# pc_heartypatch_v2_3.net
KiCad netlist of a schematic drawn in EAGLE
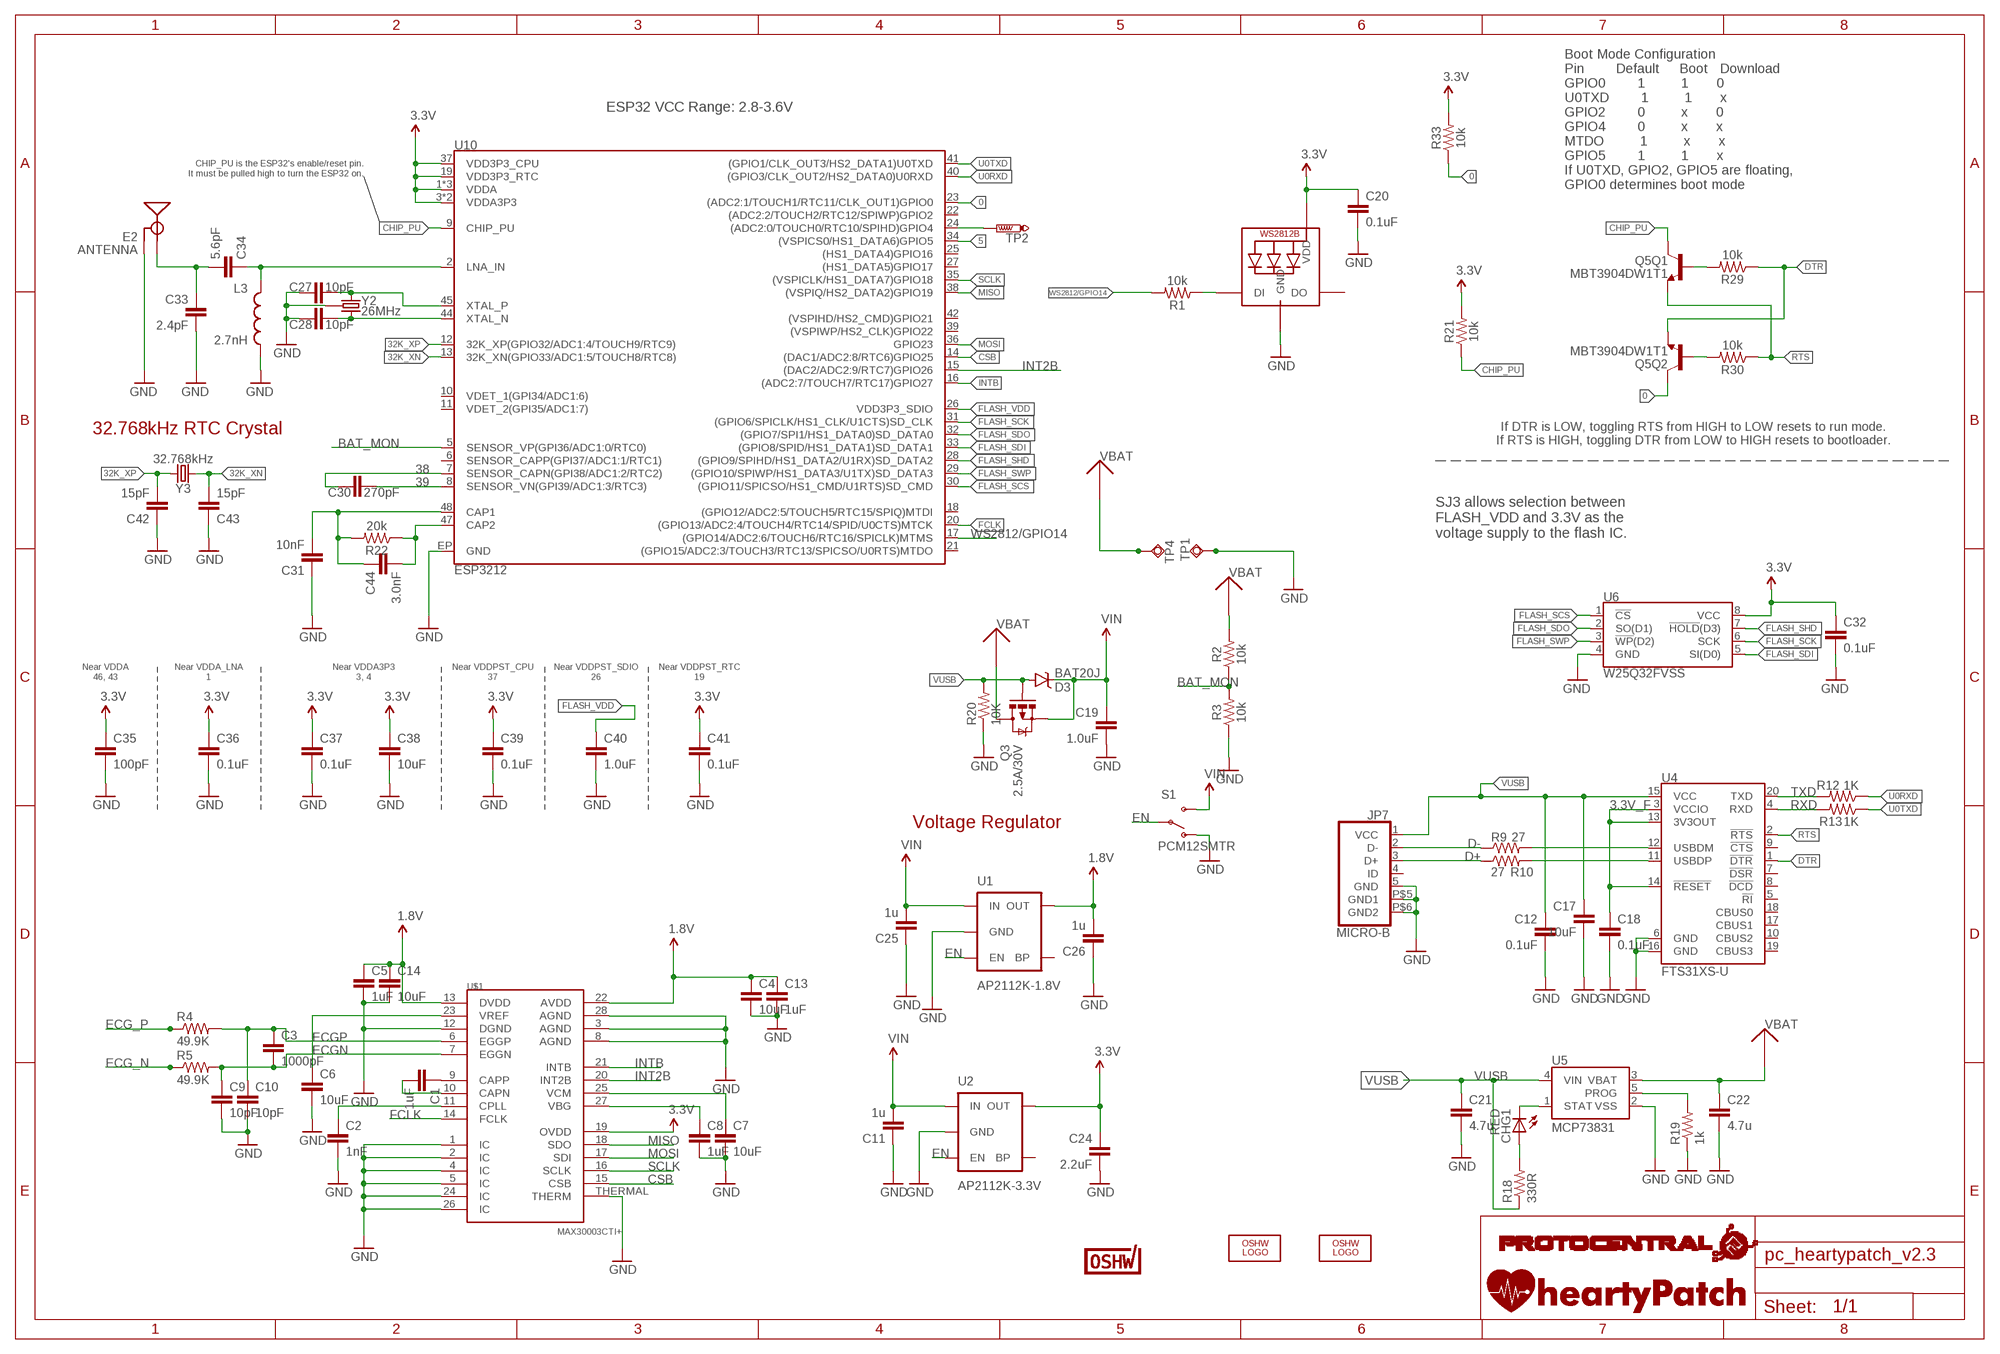
[diagram p0: schematic, sheet 1]

(export (version "E")
  (design (tool "Eeschema 10.0.6"))
  (components
    (comp (ref "C1")
      (value "1uF")
      (footprint "eagle-import:C0603")
      (libsource (lib "eagle-import") (part "C-EUC0603"))
    )
    (comp (ref "C2")
      (value "1nF")
      (footprint "eagle-import:C0603")
      (libsource (lib "eagle-import") (part "C-EUC0603"))
    )
    (comp (ref "C3")
      (value "1000pF")
      (footprint "eagle-import:C0402")
      (libsource (lib "eagle-import") (part "C-EUC0402"))
    )
    (comp (ref "C4")
      (value "10uF")
      (footprint "eagle-import:C0805")
      (libsource (lib "eagle-import") (part "C-EUC0805"))
    )
    (comp (ref "C5")
      (value "1uF")
      (footprint "eagle-import:C0402")
      (libsource (lib "eagle-import") (part "C-EUC0402"))
    )
    (comp (ref "C6")
      (value "10uF")
      (footprint "eagle-import:C0805")
      (libsource (lib "eagle-import") (part "C-EUC0805"))
    )
    (comp (ref "C7")
      (value "10uF")
      (footprint "eagle-import:C0805")
      (libsource (lib "eagle-import") (part "C-EUC0805"))
    )
    (comp (ref "C8")
      (value "1uF")
      (footprint "eagle-import:C0805")
      (libsource (lib "eagle-import") (part "C-EUC0805"))
    )
    (comp (ref "C9")
      (value "10pF")
      (footprint "eagle-import:C0402")
      (libsource (lib "eagle-import") (part "C-EUC0402"))
    )
    (comp (ref "C10")
      (value "10pF")
      (footprint "eagle-import:C0402")
      (libsource (lib "eagle-import") (part "C-EUC0402"))
    )
    (comp (ref "C11")
      (value "1u")
      (footprint "eagle-import:C0402")
      (libsource (lib "eagle-import") (part "C-EUC0402"))
    )
    (comp (ref "C12")
      (value "0.1uF")
      (footprint "eagle-import:C0402")
      (libsource (lib "eagle-import") (part "C-EUC0402"))
    )
    (comp (ref "C13")
      (value "1uF")
      (footprint "eagle-import:C0805")
      (libsource (lib "eagle-import") (part "C-EUC0805"))
    )
    (comp (ref "C14")
      (value "10uF")
      (footprint "eagle-import:C0603")
      (libsource (lib "eagle-import") (part "C-EUC0603"))
    )
    (comp (ref "C17")
      (value "10uF")
      (footprint "eagle-import:C0805")
      (libsource (lib "eagle-import") (part "C-EUC0805"))
    )
    (comp (ref "C18")
      (value "0.1uF")
      (footprint "eagle-import:C0402")
      (libsource (lib "eagle-import") (part "C-EUC0402"))
    )
    (comp (ref "C19")
      (value "1.0uF")
      (footprint "eagle-import:C0402")
      (libsource (lib "eagle-import") (part "C-EUC0402"))
    )
    (comp (ref "C20")
      (value "0.1uF")
      (footprint "eagle-import:0603")
      (libsource (lib "eagle-import") (part "0.1UF-0603-25V-(+80/-20%)"))
    )
    (comp (ref "C21")
      (value "4.7u")
      (footprint "eagle-import:C0805")
      (libsource (lib "eagle-import") (part "C-EUC0805"))
    )
    (comp (ref "C22")
      (value "4.7u")
      (footprint "eagle-import:C0805")
      (libsource (lib "eagle-import") (part "C-EUC0805"))
    )
    (comp (ref "C24")
      (value "2.2uF")
      (footprint "eagle-import:C0402")
      (libsource (lib "eagle-import") (part "C-EUC0402"))
    )
    (comp (ref "C25")
      (value "1u")
      (footprint "eagle-import:C0402")
      (libsource (lib "eagle-import") (part "C-EUC0402"))
    )
    (comp (ref "C26")
      (value "1u")
      (footprint "eagle-import:C0402")
      (libsource (lib "eagle-import") (part "C-EUC0402"))
    )
    (comp (ref "C27")
      (value "10pF")
      (footprint "eagle-import:0603")
      (libsource (lib "eagle-import") (part "10PF-0603-50V-5%"))
    )
    (comp (ref "C28")
      (value "10pF")
      (footprint "eagle-import:0603")
      (libsource (lib "eagle-import") (part "10PF-0603-50V-5%"))
    )
    (comp (ref "C30")
      (value "270pF")
      (footprint "eagle-import:0603")
      (libsource (lib "eagle-import") (part "270PF-50V-5%(0603)"))
    )
    (comp (ref "C31")
      (value "10nF")
      (footprint "eagle-import:0603")
      (libsource (lib "eagle-import") (part "10NF-0603-50V-10%"))
    )
    (comp (ref "C32")
      (value "0.1uF")
      (footprint "eagle-import:0402")
      (libsource (lib "eagle-import") (part "0.1UF-0402-16V-10%"))
    )
    (comp (ref "C33")
      (value "2.4pF")
      (footprint "eagle-import:0603")
      (libsource (lib "eagle-import") (part "2.4PF-0603-50V-5%"))
    )
    (comp (ref "C34")
      (value "5.6pF")
      (footprint "eagle-import:0603")
      (libsource (lib "eagle-import") (part "5.6PF-50V-5%(0603)"))
    )
    (comp (ref "C35")
      (value "100pF")
      (footprint "eagle-import:0603")
      (libsource (lib "eagle-import") (part "100PF-0603-50V-5%"))
    )
    (comp (ref "C36")
      (value "0.1uF")
      (footprint "eagle-import:0603")
      (libsource (lib "eagle-import") (part "0.1UF-0603-25V-(+80/-20%)"))
    )
    (comp (ref "C37")
      (value "0.1uF")
      (footprint "eagle-import:0603")
      (libsource (lib "eagle-import") (part "0.1UF-0603-25V-(+80/-20%)"))
    )
    (comp (ref "C38")
      (value "10uF")
      (footprint "eagle-import:0603")
      (libsource (lib "eagle-import") (part "10UF-0603-6.3V-20%"))
    )
    (comp (ref "C39")
      (value "0.1uF")
      (footprint "eagle-import:0402")
      (libsource (lib "eagle-import") (part "0.1UF-0402-16V-10%"))
    )
    (comp (ref "C40")
      (value "1.0uF")
      (footprint "eagle-import:0603")
      (libsource (lib "eagle-import") (part "1.0UF-0603-16V-10%"))
    )
    (comp (ref "C41")
      (value "0.1uF")
      (footprint "eagle-import:0603")
      (libsource (lib "eagle-import") (part "0.1UF-0603-25V-(+80/-20%)"))
    )
    (comp (ref "C42")
      (value "15pF")
      (footprint "eagle-import:0603")
      (libsource (lib "eagle-import") (part "15PF-0603-50V-5%"))
    )
    (comp (ref "C43")
      (value "15pF")
      (footprint "eagle-import:0603")
      (libsource (lib "eagle-import") (part "15PF-0603-50V-5%"))
    )
    (comp (ref "C44")
      (value "3.0nF")
      (footprint "eagle-import:0603")
      (libsource (lib "eagle-import") (part "3.0NF-0603-50V-5%"))
    )
    (comp (ref "CHG1")
      (value "RED")
      (footprint "eagle-import:CHIPLED_0603")
      (libsource (lib "eagle-import") (part "LEDCHIPLED_0603"))
    )
    (comp (ref "D3")
      (value "BAT20J")
      (footprint "eagle-import:SOD-323")
      (libsource (lib "eagle-import") (part "DIODE-SCHOTTKY-BAT20J"))
    )
    (comp (ref "E2")
      (value "ANTENNA")
      (footprint "eagle-import:TRACE_ANTENNA_2.4GHZ_25.7MM_TUNED")
      (libsource (lib "eagle-import") (part "ANTENNATRACE-TUNED"))
    )
    (comp (ref "JP7")
      (value "MICRO-B")
      (footprint "eagle-import:MICRO-B")
      (libsource (lib "eagle-import") (part "MICRO-B"))
    )
    (comp (ref "L3")
      (value "2.7nH")
      (footprint "eagle-import:0603")
      (libsource (lib "eagle-import") (part "INDUCTOR0603"))
    )
    (comp (ref "LED1")
      (value "WS2812B5050")
      (footprint "eagle-import:WS2812B")
      (libsource (lib "eagle-import") (part "WS2812B5050"))
    )
    (comp (ref "LOGO1")
      (value "OSHW_LOGO_FILLX0200-NT")
      (footprint "eagle-import:OSHW_FILLX200_NOTEXT")
      (libsource (lib "eagle-import") (part "OSHW_LOGO_FILLX0200-NT"))
    )
    (comp (ref "LOGO2")
      (value "OSHW_LOGO_FILLX0200-NT")
      (footprint "eagle-import:OSHW_FILLX200_NOTEXT")
      (libsource (lib "eagle-import") (part "OSHW_LOGO_FILLX0200-NT"))
    )
    (comp (ref "Q3")
      (value "2.5A/30V")
      (footprint "eagle-import:SOT23-3")
      (libsource (lib "eagle-import") (part "MOSFET-PCHANNELDMG2307L"))
    )
    (comp (ref "Q5")
      (value "MBT3904DW1T1")
      (footprint "eagle-import:SC70-6")
      (libsource (lib "eagle-import") (part "MBT3904DW1T1"))
    )
    (comp (ref "R1")
      (value "10k")
      (footprint "eagle-import:0603")
      (libsource (lib "eagle-import") (part "10KOHM-1/10W-1%(0603)0603"))
    )
    (comp (ref "R2")
      (value "10k")
      (footprint "eagle-import:0603")
      (libsource (lib "eagle-import") (part "10KOHM-1/10W-1%(0603)0603"))
    )
    (comp (ref "R3")
      (value "10k")
      (footprint "eagle-import:0603")
      (libsource (lib "eagle-import") (part "10KOHM-1/10W-1%(0603)0603"))
    )
    (comp (ref "R4")
      (value "49.9K")
      (footprint "eagle-import:0805")
      (libsource (lib "eagle-import") (part "RESISTOR0805-RES"))
    )
    (comp (ref "R5")
      (value "49.9K")
      (footprint "eagle-import:0805")
      (libsource (lib "eagle-import") (part "RESISTOR0805-RES"))
    )
    (comp (ref "R9")
      (value "27")
      (footprint "eagle-import:R0402")
      (libsource (lib "eagle-import") (part "R-US_R0402"))
    )
    (comp (ref "R10")
      (value "27")
      (footprint "eagle-import:R0402")
      (libsource (lib "eagle-import") (part "R-US_R0402"))
    )
    (comp (ref "R12")
      (value "1K")
      (footprint "eagle-import:R0402")
      (libsource (lib "eagle-import") (part "R-US_R0402"))
    )
    (comp (ref "R13")
      (value "1K")
      (footprint "eagle-import:R0402")
      (libsource (lib "eagle-import") (part "R-US_R0402"))
    )
    (comp (ref "R18")
      (value "330R")
      (footprint "eagle-import:R0402")
      (libsource (lib "eagle-import") (part "R-US_R0402"))
    )
    (comp (ref "R19")
      (value "1k")
      (footprint "eagle-import:R0402")
      (libsource (lib "eagle-import") (part "R-US_R0402"))
    )
    (comp (ref "R20")
      (value "10K")
      (footprint "eagle-import:R0402")
      (libsource (lib "eagle-import") (part "R-US_R0402"))
    )
    (comp (ref "R21")
      (value "10k")
      (footprint "eagle-import:0603")
      (libsource (lib "eagle-import") (part "10KOHM-1/10W-1%(0603)0603"))
    )
    (comp (ref "R22")
      (value "20k")
      (footprint "eagle-import:0603")
      (libsource (lib "eagle-import") (part "20KOHM-0603-1/10W-1%"))
    )
    (comp (ref "R29")
      (value "10k")
      (footprint "eagle-import:0603")
      (libsource (lib "eagle-import") (part "10KOHM-0603-1/10W-1%"))
    )
    (comp (ref "R30")
      (value "10k")
      (footprint "eagle-import:0603")
      (libsource (lib "eagle-import") (part "10KOHM-0603-1/10W-1%"))
    )
    (comp (ref "R33")
      (value "10k")
      (footprint "eagle-import:0603")
      (libsource (lib "eagle-import") (part "10KOHM-1/10W-1%(0603)0603"))
    )
    (comp (ref "S1")
      (value "PCM12SMTR")
      (footprint "eagle-import:SWITCH-SPST-SMD-A")
      (libsource (lib "eagle-import") (part "SWITCH-SPDT-SMD-A"))
    )
    (comp (ref "TP1")
      (value "TPSQTP20SQ")
      (footprint "eagle-import:TP20SQ")
      (libsource (lib "eagle-import") (part "TPSQTP20SQ"))
    )
    (comp (ref "TP2")
      (value "PTR1TP10SQ")
      (footprint "eagle-import:TP10SQ")
      (libsource (lib "eagle-import") (part "PTR1TP10SQ"))
    )
    (comp (ref "TP4")
      (value "TPSQTP20SQ")
      (footprint "eagle-import:TP20SQ")
      (libsource (lib "eagle-import") (part "TPSQTP20SQ"))
    )
    (comp (ref "U$1")
      (value "MAX30003CTI+")
      (footprint "eagle-import:QFN-28")
      (libsource (lib "eagle-import") (part "MAX30003"))
    )
    (comp (ref "U$8")
      (value "HEARTYPATCHHEART")
      (footprint "eagle-import:HEARTYPATCH")
      (libsource (lib "eagle-import") (part "HEARTYPATCHHEART"))
    )
    (comp (ref "U$9")
      (value "PROTY_LOGO_WITH_TEXT")
      (footprint "eagle-import:PROTY_WITH_TEXT")
      (libsource (lib "eagle-import") (part "PROTY_LOGO_WITH_TEXT"))
    )
    (comp (ref "U$10")
      (value "CERT-SMALL")
      (footprint "eagle-import:CERT-SMALL-SILK")
      (libsource (lib "eagle-import") (part "CERT-SMALL"))
    )
    (comp (ref "U1")
      (value "AP2112K-1.8V")
      (footprint "eagle-import:SOT23-5")
      (libsource (lib "eagle-import") (part "V_REG_LDOSMD"))
    )
    (comp (ref "U2")
      (value "AP2112K-3.3V")
      (footprint "eagle-import:SOT23-5")
      (libsource (lib "eagle-import") (part "V_REG_LDOSMD"))
    )
    (comp (ref "U4")
      (value "FTS31XS-U")
      (footprint "eagle-import:SSOP20_L")
      (libsource (lib "eagle-import") (part "FT231XS"))
    )
    (comp (ref "U5")
      (value "MCP73831")
      (footprint "eagle-import:SOT23-5")
      (libsource (lib "eagle-import") (part "MCP73831"))
    )
    (comp (ref "U6")
      (value "W25Q32FVSS")
      (footprint "eagle-import:SOIC-8")
      (libsource (lib "eagle-import") (part "W25Q32FVSS"))
    )
    (comp (ref "U10")
      (value "ESP3212")
      (footprint "eagle-import:QFN48-0.4MM")
      (libsource (lib "eagle-import") (part "ESP3212"))
    )
    (comp (ref "Y2")
      (value "26MHz")
      (footprint "eagle-import:CRYSTAL-SMD-3.2X2.5")
      (libsource (lib "eagle-import") (part "CRYSTAL-GROUNDED3.2X2.5"))
    )
    (comp (ref "Y3")
      (value "32.768kHz")
      (footprint "eagle-import:CRYSTAL-SMD-3.2X1.5MM")
      (libsource (lib "eagle-import") (part "CRYSTAL-32.768KHZSMD-3.2X1.5"))
    )
  )
  (nets
    (net (code "1") (name "/3.3V_F") (class "Default")
      (node (ref "C18") (pin "1") (pinfunction "1_1") (pintype "passive"))
      (node (ref "U4") (pin "13") (pinfunction "3V3OUT_13") (pintype "bidirectional"))
      (node (ref "U4") (pin "14") (pinfunction "~{RESET}_14") (pintype "bidirectional"))
      (node (ref "U4") (pin "3") (pinfunction "VCCIO_3") (pintype "bidirectional"))
    )
    (net (code "2") (name "/38") (class "Default")
      (node (ref "C30") (pin "1") (pinfunction "1_1") (pintype "passive"))
      (node (ref "U10") (pin "7") (pinfunction "SENSOR_CAPN(GPI38/ADC1:2/RTC2)_7") (pintype "bidirectional"))
    )
    (net (code "3") (name "/39") (class "Default")
      (node (ref "C30") (pin "2") (pinfunction "2_2") (pintype "passive"))
      (node (ref "U10") (pin "8") (pinfunction "SENSOR_VN(GPI39/ADC1:3/RTC3)_8") (pintype "bidirectional"))
    )
    (net (code "4") (name "/BAT_MON") (class "Default")
      (node (ref "R2") (pin "1") (pinfunction "1_1") (pintype "passive"))
      (node (ref "R3") (pin "2") (pinfunction "2_2") (pintype "passive"))
      (node (ref "U10") (pin "5") (pinfunction "SENSOR_VP(GPI36/ADC1:0/RTC0)_5") (pintype "bidirectional"))
    )
    (net (code "5") (name "/D+") (class "Default")
      (node (ref "JP7") (pin "3") (pinfunction "D+_3") (pintype "bidirectional"))
      (node (ref "R10") (pin "1") (pinfunction "1_1") (pintype "passive"))
    )
    (net (code "6") (name "/D-") (class "Default")
      (node (ref "JP7") (pin "2") (pinfunction "D-_2") (pintype "bidirectional"))
      (node (ref "R9") (pin "1") (pinfunction "1_1") (pintype "passive"))
    )
    (net (code "7") (name "/ECGN") (class "Default")
      (node (ref "C3") (pin "2") (pinfunction "2_2") (pintype "passive"))
      (node (ref "C9") (pin "1") (pinfunction "1_1") (pintype "passive"))
      (node (ref "R5") (pin "2") (pinfunction "2_2") (pintype "passive"))
      (node (ref "U$1") (pin "7") (pinfunction "EGGN_7") (pintype "bidirectional"))
    )
    (net (code "8") (name "/ECGP") (class "Default")
      (node (ref "C10") (pin "1") (pinfunction "1_1") (pintype "passive"))
      (node (ref "C3") (pin "1") (pinfunction "1_1") (pintype "passive"))
      (node (ref "R4") (pin "2") (pinfunction "2_2") (pintype "passive"))
      (node (ref "U$1") (pin "6") (pinfunction "EGGP_6") (pintype "bidirectional"))
    )
    (net (code "9") (name "/ECG_N") (class "Default")
      (node (ref "R5") (pin "1") (pinfunction "1_1") (pintype "passive"))
    )
    (net (code "10") (name "/ECG_P") (class "Default")
      (node (ref "R4") (pin "1") (pinfunction "1_1") (pintype "passive"))
    )
    (net (code "11") (name "/EN") (class "Default")
      (node (ref "S1") (pin "2") (pinfunction "P_2") (pintype "passive"))
      (node (ref "U1") (pin "3") (pinfunction "EN_3") (pintype "input"))
      (node (ref "U2") (pin "3") (pinfunction "EN_3") (pintype "input"))
    )
    (net (code "12") (name "/INT2B") (class "Default")
      (node (ref "U$1") (pin "20") (pinfunction "INT2B_20") (pintype "bidirectional"))
      (node (ref "U10") (pin "15") (pinfunction "(DAC2/ADC2:9/RTC7)GPIO26_15") (pintype "bidirectional"))
    )
    (net (code "13") (name "/RXD") (class "Default")
      (node (ref "R13") (pin "2") (pinfunction "2_2") (pintype "passive"))
      (node (ref "U4") (pin "4") (pinfunction "RXD_4") (pintype "bidirectional"))
    )
    (net (code "14") (name "/TXD") (class "Default")
      (node (ref "R12") (pin "2") (pinfunction "2_2") (pintype "passive"))
      (node (ref "U4") (pin "20") (pinfunction "TXD_20") (pintype "bidirectional"))
    )
    (net (code "15") (name "0") (class "Default")
      (node (ref "Q5") (pin "6") (pinfunction "C_6") (pintype "passive"))
      (node (ref "R33") (pin "1") (pinfunction "1_1") (pintype "passive"))
      (node (ref "U10") (pin "23") (pinfunction "(ADC2:1/TOUCH1/RTC11/CLK_OUT1)GPIO0_23") (pintype "bidirectional"))
    )
    (net (code "16") (name "1.8V") (class "Default")
      (node (ref "C13") (pin "1") (pinfunction "1_1") (pintype "passive"))
      (node (ref "C14") (pin "1") (pinfunction "1_1") (pintype "passive"))
      (node (ref "C26") (pin "2") (pinfunction "2_2") (pintype "passive"))
      (node (ref "C4") (pin "1") (pinfunction "1_1") (pintype "passive"))
      (node (ref "C5") (pin "1") (pinfunction "1_1") (pintype "passive"))
      (node (ref "U$1") (pin "13") (pinfunction "DVDD_13") (pintype "bidirectional"))
      (node (ref "U$1") (pin "22") (pinfunction "AVDD_22") (pintype "bidirectional"))
      (node (ref "U1") (pin "5") (pinfunction "OUT_5") (pintype "passive"))
    )
    (net (code "17") (name "3.3V") (class "Default")
      (node (ref "C20") (pin "1") (pinfunction "1_1") (pintype "passive"))
      (node (ref "C24") (pin "1") (pinfunction "1_1") (pintype "passive"))
      (node (ref "C32") (pin "1") (pinfunction "1_1") (pintype "passive"))
      (node (ref "C35") (pin "1") (pinfunction "1_1") (pintype "passive"))
      (node (ref "C36") (pin "1") (pinfunction "1_1") (pintype "passive"))
      (node (ref "C37") (pin "1") (pinfunction "1_1") (pintype "passive"))
      (node (ref "C38") (pin "1") (pinfunction "1_1") (pintype "passive"))
      (node (ref "C39") (pin "1") (pinfunction "1_1") (pintype "passive"))
      (node (ref "C41") (pin "1") (pinfunction "1_1") (pintype "passive"))
      (node (ref "LED1") (pin "1-VDD") (pinfunction "VDD_1-VDD") (pintype "power_in"))
      (node (ref "R21") (pin "2") (pinfunction "2_2") (pintype "passive"))
      (node (ref "R33") (pin "2") (pinfunction "2_2") (pintype "passive"))
      (node (ref "U$1") (pin "19") (pinfunction "OVDD_19") (pintype "bidirectional"))
      (node (ref "U10") (pin "1") (pinfunction "VDDA_1") (pintype "bidirectional"))
      (node (ref "U10") (pin "19") (pinfunction "VDD3P3_RTC_19") (pintype "bidirectional"))
      (node (ref "U10") (pin "3") (pinfunction "VDDA3P3_3") (pintype "bidirectional"))
      (node (ref "U10") (pin "37") (pinfunction "VDD3P3_CPU_37") (pintype "bidirectional"))
      (node (ref "U10") (pin "4") (pinfunction "VDDA3P3_4") (pintype "bidirectional"))
      (node (ref "U10") (pin "43") (pinfunction "VDDA_43") (pintype "bidirectional"))
      (node (ref "U10") (pin "46") (pinfunction "VDDA_46") (pintype "bidirectional"))
      (node (ref "U2") (pin "5") (pinfunction "OUT_5") (pintype "passive"))
      (node (ref "U6") (pin "8") (pinfunction "VCC_8") (pintype "bidirectional"))
    )
    (net (code "18") (name "5") (class "Default")
      (node (ref "U10") (pin "34") (pinfunction "(VSPICS0/HS1_DATA6)GPIO5_34") (pintype "bidirectional"))
    )
    (net (code "19") (name "32K_XN") (class "Default")
      (node (ref "C43") (pin "2") (pinfunction "2_2") (pintype "passive"))
      (node (ref "U10") (pin "13") (pinfunction "32K_XN(GPIO33/ADC1:5/TOUCH8/RTC8)_13") (pintype "bidirectional"))
      (node (ref "Y3") (pin "P$2") (pinfunction "2_P$2") (pintype "passive"))
    )
    (net (code "20") (name "32K_XP") (class "Default")
      (node (ref "C42") (pin "2") (pinfunction "2_2") (pintype "passive"))
      (node (ref "U10") (pin "12") (pinfunction "32K_XP(GPIO32/ADC1:4/TOUCH9/RTC9)_12") (pintype "bidirectional"))
      (node (ref "Y3") (pin "P$1") (pinfunction "1_P$1") (pintype "passive"))
    )
    (net (code "21") (name "CHIP_PU") (class "Default")
      (node (ref "Q5") (pin "3") (pinfunction "C_3") (pintype "passive"))
      (node (ref "R21") (pin "1") (pinfunction "1_1") (pintype "passive"))
      (node (ref "U10") (pin "9") (pinfunction "CHIP_PU_9") (pintype "bidirectional"))
    )
    (net (code "22") (name "CSB") (class "Default")
      (node (ref "U$1") (pin "15") (pinfunction "CSB_15") (pintype "bidirectional"))
      (node (ref "U10") (pin "14") (pinfunction "(DAC1/ADC2:8/RTC6)GPIO25_14") (pintype "bidirectional"))
    )
    (net (code "23") (name "DTR") (class "Default")
      (node (ref "Q5") (pin "1") (pinfunction "E_1") (pintype "passive"))
      (node (ref "R29") (pin "1") (pinfunction "1_1") (pintype "passive"))
      (node (ref "U4") (pin "1") (pinfunction "~{DTR}_1") (pintype "bidirectional"))
    )
    (net (code "24") (name "FCLK") (class "Default")
      (node (ref "U$1") (pin "14") (pinfunction "FCLK_14") (pintype "bidirectional"))
      (node (ref "U10") (pin "20") (pinfunction "(GPIO13/ADC2:4/TOUCH4/RTC14/SPID/U0CTS)MTCK_20") (pintype "bidirectional"))
    )
    (net (code "25") (name "FLASH_SCK") (class "Default")
      (node (ref "U10") (pin "31") (pinfunction "(GPIO6/SPICLK/HS1_CLK/U1CTS)SD_CLK_31") (pintype "bidirectional"))
      (node (ref "U6") (pin "6") (pinfunction "SCK_6") (pintype "bidirectional"))
    )
    (net (code "26") (name "FLASH_SCS") (class "Default")
      (node (ref "U10") (pin "30") (pinfunction "(GPIO11/SPICSO/HS1_CMD/U1RTS)SD_CMD_30") (pintype "bidirectional"))
      (node (ref "U6") (pin "1") (pinfunction "~{CS}_1") (pintype "bidirectional"))
    )
    (net (code "27") (name "FLASH_SDI") (class "Default")
      (node (ref "U10") (pin "33") (pinfunction "(GPIO8/SPID/HS1_DATA1)SD_DATA1_33") (pintype "bidirectional"))
      (node (ref "U6") (pin "5") (pinfunction "SI(D0)_5") (pintype "bidirectional"))
    )
    (net (code "28") (name "FLASH_SDO") (class "Default")
      (node (ref "U10") (pin "32") (pinfunction "(GPIO7/SPI1/HS1_DATA0)SD_DATA0_32") (pintype "bidirectional"))
      (node (ref "U6") (pin "2") (pinfunction "SO(D1)_2") (pintype "bidirectional"))
    )
    (net (code "29") (name "FLASH_SHD") (class "Default")
      (node (ref "U10") (pin "28") (pinfunction "(GPIO9/SPIHD/HS1_DATA2/U1RX)SD_DATA2_28") (pintype "bidirectional"))
      (node (ref "U6") (pin "7") (pinfunction "~{HOLD}(D3)_7") (pintype "bidirectional"))
    )
    (net (code "30") (name "FLASH_SWP") (class "Default")
      (node (ref "U10") (pin "29") (pinfunction "(GPIO10/SPIWP/HS1_DATA3/U1TX)SD_DATA3_29") (pintype "bidirectional"))
      (node (ref "U6") (pin "3") (pinfunction "~{WP}(D2)_3") (pintype "bidirectional"))
    )
    (net (code "31") (name "FLASH_VDD") (class "Default")
      (node (ref "C40") (pin "1") (pinfunction "1_1") (pintype "passive"))
      (node (ref "U10") (pin "26") (pinfunction "VDD3P3_SDIO_26") (pintype "bidirectional"))
    )
    (net (code "32") (name "GND") (class "Default")
      (node (ref "C10") (pin "2") (pinfunction "2_2") (pintype "passive"))
      (node (ref "C11") (pin "1") (pinfunction "1_1") (pintype "passive"))
      (node (ref "C12") (pin "2") (pinfunction "2_2") (pintype "passive"))
      (node (ref "C13") (pin "2") (pinfunction "2_2") (pintype "passive"))
      (node (ref "C14") (pin "2") (pinfunction "2_2") (pintype "passive"))
      (node (ref "C17") (pin "2") (pinfunction "2_2") (pintype "passive"))
      (node (ref "C18") (pin "2") (pinfunction "2_2") (pintype "passive"))
      (node (ref "C19") (pin "2") (pinfunction "2_2") (pintype "passive"))
      (node (ref "C2") (pin "2") (pinfunction "2_2") (pintype "passive"))
      (node (ref "C20") (pin "2") (pinfunction "2_2") (pintype "passive"))
      (node (ref "C21") (pin "2") (pinfunction "2_2") (pintype "passive"))
      (node (ref "C22") (pin "2") (pinfunction "2_2") (pintype "passive"))
      (node (ref "C24") (pin "2") (pinfunction "2_2") (pintype "passive"))
      (node (ref "C25") (pin "1") (pinfunction "1_1") (pintype "passive"))
      (node (ref "C26") (pin "1") (pinfunction "1_1") (pintype "passive"))
      (node (ref "C27") (pin "1") (pinfunction "1_1") (pintype "passive"))
      (node (ref "C28") (pin "1") (pinfunction "1_1") (pintype "passive"))
      (node (ref "C31") (pin "1") (pinfunction "1_1") (pintype "passive"))
      (node (ref "C32") (pin "2") (pinfunction "2_2") (pintype "passive"))
      (node (ref "C33") (pin "2") (pinfunction "2_2") (pintype "passive"))
      (node (ref "C35") (pin "2") (pinfunction "2_2") (pintype "passive"))
      (node (ref "C36") (pin "2") (pinfunction "2_2") (pintype "passive"))
      (node (ref "C37") (pin "2") (pinfunction "2_2") (pintype "passive"))
      (node (ref "C38") (pin "2") (pinfunction "2_2") (pintype "passive"))
      (node (ref "C39") (pin "2") (pinfunction "2_2") (pintype "passive"))
      (node (ref "C4") (pin "2") (pinfunction "2_2") (pintype "passive"))
      (node (ref "C40") (pin "2") (pinfunction "2_2") (pintype "passive"))
      (node (ref "C41") (pin "2") (pinfunction "2_2") (pintype "passive"))
      (node (ref "C42") (pin "1") (pinfunction "1_1") (pintype "passive"))
      (node (ref "C43") (pin "1") (pinfunction "1_1") (pintype "passive"))
      (node (ref "C5") (pin "2") (pinfunction "2_2") (pintype "passive"))
      (node (ref "C6") (pin "2") (pinfunction "2_2") (pintype "passive"))
      (node (ref "C7") (pin "2") (pinfunction "2_2") (pintype "passive"))
      (node (ref "C8") (pin "2") (pinfunction "2_2") (pintype "passive"))
      (node (ref "C9") (pin "2") (pinfunction "2_2") (pintype "passive"))
      (node (ref "E2") (pin "GND") (pinfunction "GND_GND") (pintype "bidirectional"))
      (node (ref "E2") (pin "GND2") (pinfunction "GND_GND2") (pintype "bidirectional"))
      (node (ref "JP7") (pin "5") (pinfunction "GND_5") (pintype "bidirectional"))
      (node (ref "JP7") (pin "P$5") (pinfunction "GND1_P$5") (pintype "bidirectional"))
      (node (ref "JP7") (pin "P$6") (pinfunction "GND2_P$6") (pintype "bidirectional"))
      (node (ref "L3") (pin "2") (pinfunction "2_2") (pintype "passive"))
      (node (ref "LED1") (pin "3-GND") (pinfunction "GND_3-GND") (pintype "power_in"))
      (node (ref "R19") (pin "1") (pinfunction "1_1") (pintype "passive"))
      (node (ref "R20") (pin "1") (pinfunction "1_1") (pintype "passive"))
      (node (ref "R3") (pin "1") (pinfunction "1_1") (pintype "passive"))
      (node (ref "S1") (pin "1") (pinfunction "O_1") (pintype "passive"))
      (node (ref "TP1") (pin "TP") (pinfunction "TP_TP") (pintype "input"))
      (node (ref "U$1") (pin "1") (pinfunction "IC_1") (pintype "bidirectional"))
      (node (ref "U$1") (pin "12") (pinfunction "DGND_12") (pintype "bidirectional"))
      (node (ref "U$1") (pin "2") (pinfunction "IC_2") (pintype "bidirectional"))
      (node (ref "U$1") (pin "24") (pinfunction "IC_24") (pintype "bidirectional"))
      (node (ref "U$1") (pin "26") (pinfunction "IC_26") (pintype "bidirectional"))
      (node (ref "U$1") (pin "28") (pinfunction "AGND_28") (pintype "bidirectional"))
      (node (ref "U$1") (pin "3") (pinfunction "AGND_3") (pintype "bidirectional"))
      (node (ref "U$1") (pin "4") (pinfunction "IC_4") (pintype "bidirectional"))
      (node (ref "U$1") (pin "5") (pinfunction "IC_5") (pintype "bidirectional"))
      (node (ref "U$1") (pin "8") (pinfunction "AGND_8") (pintype "bidirectional"))
      (node (ref "U$1") (pin "THERMAL") (pinfunction "THERM_THERMAL") (pintype "bidirectional"))
      (node (ref "U1") (pin "2") (pinfunction "GND_2") (pintype "input"))
      (node (ref "U10") (pin "EP") (pinfunction "GND_EP") (pintype "bidirectional"))
      (node (ref "U2") (pin "2") (pinfunction "GND_2") (pintype "input"))
      (node (ref "U4") (pin "16") (pinfunction "GND_16") (pintype "bidirectional"))
      (node (ref "U4") (pin "6") (pinfunction "GND_6") (pintype "bidirectional"))
      (node (ref "U5") (pin "2") (pinfunction "VSS_2") (pintype "power_in"))
      (node (ref "U6") (pin "4") (pinfunction "GND_4") (pintype "bidirectional"))
      (node (ref "Y2") (pin "2") (pinfunction "GND_2") (pintype "passive"))
      (node (ref "Y2") (pin "4") (pinfunction "GND_4") (pintype "passive"))
    )
    (net (code "33") (name "INTB") (class "Default")
      (node (ref "U$1") (pin "21") (pinfunction "INTB_21") (pintype "bidirectional"))
      (node (ref "U10") (pin "16") (pinfunction "(ADC2:7/TOUCH7/RTC17)GPIO27_16") (pintype "bidirectional"))
    )
    (net (code "34") (name "MISO") (class "Default")
      (node (ref "U$1") (pin "18") (pinfunction "SDO_18") (pintype "bidirectional"))
      (node (ref "U10") (pin "38") (pinfunction "(VSPIQ/HS2_DATA2)GPIO19_38") (pintype "bidirectional"))
    )
    (net (code "35") (name "MOSI") (class "Default")
      (node (ref "U$1") (pin "17") (pinfunction "SDI_17") (pintype "bidirectional"))
      (node (ref "U10") (pin "36") (pinfunction "GPIO23_36") (pintype "bidirectional"))
    )
    (net (code "36") (name "Net-(CHG1-PadA)") (class "Default")
      (node (ref "CHG1") (pin "A") (pinfunction "A_A") (pintype "passive"))
      (node (ref "R18") (pin "2") (pinfunction "2_2") (pintype "passive"))
    )
    (net (code "37") (name "Net-(E2-SIGNAL)") (class "Default")
      (node (ref "C33") (pin "1") (pinfunction "1_1") (pintype "passive"))
      (node (ref "C34") (pin "2") (pinfunction "2_2") (pintype "passive"))
      (node (ref "E2") (pin "ANT") (pinfunction "SIGNAL_ANT") (pintype "bidirectional"))
    )
    (net (code "38") (name "Net-(LED1-DI)") (class "Default")
      (node (ref "LED1") (pin "4-DIN") (pinfunction "DI_4-DIN") (pintype "input"))
      (node (ref "R1") (pin "1") (pinfunction "1_1") (pintype "passive"))
    )
    (net (code "39") (name "Net-(Q5A-B)") (class "Default")
      (node (ref "Q5") (pin "5") (pinfunction "B_5") (pintype "passive"))
      (node (ref "R29") (pin "2") (pinfunction "2_2") (pintype "passive"))
    )
    (net (code "40") (name "Net-(Q5B-B)") (class "Default")
      (node (ref "Q5") (pin "2") (pinfunction "B_2") (pintype "passive"))
      (node (ref "R30") (pin "2") (pinfunction "2_2") (pintype "passive"))
    )
    (net (code "41") (name "Net-(U$1-CAPN)") (class "Default")
      (node (ref "C1") (pin "2") (pinfunction "2_2") (pintype "passive"))
      (node (ref "U$1") (pin "10") (pinfunction "CAPN_10") (pintype "bidirectional"))
    )
    (net (code "42") (name "Net-(U$1-CAPP)") (class "Default")
      (node (ref "C1") (pin "1") (pinfunction "1_1") (pintype "passive"))
      (node (ref "U$1") (pin "9") (pinfunction "CAPP_9") (pintype "bidirectional"))
    )
    (net (code "43") (name "Net-(U$1-CPLL)") (class "Default")
      (node (ref "C2") (pin "1") (pinfunction "1_1") (pintype "passive"))
      (node (ref "U$1") (pin "11") (pinfunction "CPLL_11") (pintype "bidirectional"))
    )
    (net (code "44") (name "Net-(U$1-VBG)") (class "Default")
      (node (ref "C8") (pin "1") (pinfunction "1_1") (pintype "passive"))
      (node (ref "U$1") (pin "27") (pinfunction "VBG_27") (pintype "bidirectional"))
    )
    (net (code "45") (name "Net-(U$1-VCM)") (class "Default")
      (node (ref "C7") (pin "1") (pinfunction "1_1") (pintype "passive"))
      (node (ref "U$1") (pin "25") (pinfunction "VCM_25") (pintype "bidirectional"))
    )
    (net (code "46") (name "Net-(U$1-VREF)") (class "Default")
      (node (ref "C6") (pin "1") (pinfunction "1_1") (pintype "passive"))
      (node (ref "U$1") (pin "23") (pinfunction "VREF_23") (pintype "bidirectional"))
    )
    (net (code "47") (name "Net-(U4-USBDM)") (class "Default")
      (node (ref "R9") (pin "2") (pinfunction "2_2") (pintype "passive"))
      (node (ref "U4") (pin "12") (pinfunction "USBDM_12") (pintype "bidirectional"))
    )
    (net (code "48") (name "Net-(U4-USBDP)") (class "Default")
      (node (ref "R10") (pin "2") (pinfunction "2_2") (pintype "passive"))
      (node (ref "U4") (pin "11") (pinfunction "USBDP_11") (pintype "bidirectional"))
    )
    (net (code "49") (name "Net-(U5-PROG)") (class "Default")
      (node (ref "R19") (pin "2") (pinfunction "2_2") (pintype "passive"))
      (node (ref "U5") (pin "5") (pinfunction "PROG_5") (pintype "input"))
    )
    (net (code "50") (name "Net-(U5-STAT)") (class "Default")
      (node (ref "CHG1") (pin "C") (pinfunction "C_C") (pintype "passive"))
      (node (ref "U5") (pin "1") (pinfunction "STAT_1") (pintype "output"))
    )
    (net (code "51") (name "Net-(U10-(ADC2:0{slash}TOUCH0{slash}RTC10{slash}SPIHD)GPIO4)") (class "Default")
      (node (ref "TP2") (pin "TP") (pinfunction "TP_TP") (pintype "input"))
      (node (ref "U10") (pin "24") (pinfunction "(ADC2:0/TOUCH0/RTC10/SPIHD)GPIO4_24") (pintype "bidirectional"))
    )
    (net (code "52") (name "Net-(U10-CAP1)") (class "Default")
      (node (ref "C31") (pin "2") (pinfunction "2_2") (pintype "passive"))
      (node (ref "C44") (pin "1") (pinfunction "1_1") (pintype "passive"))
      (node (ref "R22") (pin "2") (pinfunction "2_2") (pintype "passive"))
      (node (ref "U10") (pin "48") (pinfunction "CAP1_48") (pintype "bidirectional"))
    )
    (net (code "53") (name "Net-(U10-CAP2)") (class "Default")
      (node (ref "C44") (pin "2") (pinfunction "2_2") (pintype "passive"))
      (node (ref "R22") (pin "1") (pinfunction "1_1") (pintype "passive"))
      (node (ref "U10") (pin "47") (pinfunction "CAP2_47") (pintype "bidirectional"))
    )
    (net (code "54") (name "Net-(U10-LNA_IN)") (class "Default")
      (node (ref "C34") (pin "1") (pinfunction "1_1") (pintype "passive"))
      (node (ref "L3") (pin "1") (pinfunction "1_1") (pintype "passive"))
      (node (ref "U10") (pin "2") (pinfunction "LNA_IN_2") (pintype "bidirectional"))
    )
    (net (code "55") (name "Net-(U10-XTAL_N)") (class "Default")
      (node (ref "C28") (pin "2") (pinfunction "2_2") (pintype "passive"))
      (node (ref "U10") (pin "44") (pinfunction "XTAL_N_44") (pintype "bidirectional"))
      (node (ref "Y2") (pin "3") (pinfunction "2_3") (pintype "passive"))
    )
    (net (code "56") (name "Net-(U10-XTAL_P)") (class "Default")
      (node (ref "C27") (pin "2") (pinfunction "2_2") (pintype "passive"))
      (node (ref "U10") (pin "45") (pinfunction "XTAL_P_45") (pintype "bidirectional"))
      (node (ref "Y2") (pin "1") (pinfunction "1_1") (pintype "passive"))
    )
    (net (code "57") (name "RTS") (class "Default")
      (node (ref "Q5") (pin "4") (pinfunction "E_4") (pintype "passive"))
      (node (ref "R30") (pin "1") (pinfunction "1_1") (pintype "passive"))
      (node (ref "U4") (pin "2") (pinfunction "~{RTS}_2") (pintype "bidirectional"))
    )
    (net (code "58") (name "SCLK") (class "Default")
      (node (ref "U$1") (pin "16") (pinfunction "SCLK_16") (pintype "bidirectional"))
      (node (ref "U10") (pin "35") (pinfunction "(VSPICLK/HS1_DATA7)GPIO18_35") (pintype "bidirectional"))
    )
    (net (code "59") (name "U0RXD") (class "Default")
      (node (ref "R12") (pin "1") (pinfunction "1_1") (pintype "passive"))
      (node (ref "U10") (pin "40") (pinfunction "(GPIO3/CLK_OUT2/HS2_DATA0)U0RXD_40") (pintype "bidirectional"))
    )
    (net (code "60") (name "U0TXD") (class "Default")
      (node (ref "R13") (pin "1") (pinfunction "1_1") (pintype "passive"))
      (node (ref "U10") (pin "41") (pinfunction "(GPIO1/CLK_OUT3/HS2_DATA1)U0TXD_41") (pintype "bidirectional"))
    )
    (net (code "61") (name "VBAT") (class "Default")
      (node (ref "C22") (pin "1") (pinfunction "1_1") (pintype "passive"))
      (node (ref "Q3") (pin "3") (pinfunction "D_3") (pintype "passive"))
      (node (ref "R2") (pin "2") (pinfunction "2_2") (pintype "passive"))
      (node (ref "TP4") (pin "TP") (pinfunction "TP_TP") (pintype "input"))
      (node (ref "U5") (pin "3") (pinfunction "VBAT_3") (pintype "power_in"))
    )
    (net (code "62") (name "VIN") (class "Default")
      (node (ref "C11") (pin "2") (pinfunction "2_2") (pintype "passive"))
      (node (ref "C19") (pin "1") (pinfunction "1_1") (pintype "passive"))
      (node (ref "C25") (pin "2") (pinfunction "2_2") (pintype "passive"))
      (node (ref "D3") (pin "C") (pinfunction "C_C") (pintype "passive"))
      (node (ref "Q3") (pin "2") (pinfunction "S_2") (pintype "passive"))
      (node (ref "S1") (pin "3") (pinfunction "S_3") (pintype "passive"))
      (node (ref "U1") (pin "1") (pinfunction "IN_1") (pintype "input"))
      (node (ref "U2") (pin "1") (pinfunction "IN_1") (pintype "input"))
    )
    (net (code "63") (name "VUSB") (class "Default")
      (node (ref "C12") (pin "1") (pinfunction "1_1") (pintype "passive"))
      (node (ref "C17") (pin "1") (pinfunction "1_1") (pintype "passive"))
      (node (ref "C21") (pin "1") (pinfunction "1_1") (pintype "passive"))
      (node (ref "D3") (pin "A") (pinfunction "A_A") (pintype "passive"))
      (node (ref "JP7") (pin "1") (pinfunction "VCC_1") (pintype "bidirectional"))
      (node (ref "Q3") (pin "1") (pinfunction "G_1") (pintype "passive"))
      (node (ref "R18") (pin "1") (pinfunction "1_1") (pintype "passive"))
      (node (ref "R20") (pin "2") (pinfunction "2_2") (pintype "passive"))
      (node (ref "U4") (pin "15") (pinfunction "VCC_15") (pintype "bidirectional"))
      (node (ref "U5") (pin "4") (pinfunction "VIN_4") (pintype "power_in"))
    )
    (net (code "64") (name "WS2812{slash}GPIO14") (class "Default")
      (node (ref "R1") (pin "2") (pinfunction "2_2") (pintype "passive"))
      (node (ref "U10") (pin "17") (pinfunction "(GPIO14/ADC2:6/TOUCH6/RTC16/SPICLK)MTMS_17") (pintype "bidirectional"))
    )
    (net (code "65") (name "unconnected-(JP7-ID-Pad4)") (class "Default")
      (node (ref "JP7") (pin "4") (pinfunction "ID_4") (pintype "bidirectional"))
    )
    (net (code "66") (name "unconnected-(LED1-DO-Pad2-DOUT)") (class "Default")
      (node (ref "LED1") (pin "2-DOUT") (pinfunction "DO_2-DOUT") (pintype "output"))
    )
    (net (code "67") (name "unconnected-(U1-BP-Pad4)") (class "Default")
      (node (ref "U1") (pin "4") (pinfunction "BP_4") (pintype "input"))
    )
    (net (code "68") (name "unconnected-(U2-BP-Pad4)") (class "Default")
      (node (ref "U2") (pin "4") (pinfunction "BP_4") (pintype "input"))
    )
    (net (code "69") (name "unconnected-(U4-CBUS0-Pad18)") (class "Default")
      (node (ref "U4") (pin "18") (pinfunction "CBUS0_18") (pintype "bidirectional"))
    )
    (net (code "70") (name "unconnected-(U4-CBUS1-Pad17)") (class "Default")
      (node (ref "U4") (pin "17") (pinfunction "CBUS1_17") (pintype "bidirectional"))
    )
    (net (code "71") (name "unconnected-(U4-CBUS2-Pad10)") (class "Default")
      (node (ref "U4") (pin "10") (pinfunction "CBUS2_10") (pintype "bidirectional"))
    )
    (net (code "72") (name "unconnected-(U4-CBUS3-Pad19)") (class "Default")
      (node (ref "U4") (pin "19") (pinfunction "CBUS3_19") (pintype "bidirectional"))
    )
    (net (code "73") (name "unconnected-(U4-~{CTS}-Pad9)") (class "Default")
      (node (ref "U4") (pin "9") (pinfunction "~{CTS}_9") (pintype "bidirectional"))
    )
    (net (code "74") (name "unconnected-(U4-~{DCD}-Pad8)") (class "Default")
      (node (ref "U4") (pin "8") (pinfunction "~{DCD}_8") (pintype "bidirectional"))
    )
    (net (code "75") (name "unconnected-(U4-~{DSR}-Pad7)") (class "Default")
      (node (ref "U4") (pin "7") (pinfunction "~{DSR}_7") (pintype "bidirectional"))
    )
    (net (code "76") (name "unconnected-(U4-~{RI}-Pad5)") (class "Default")
      (node (ref "U4") (pin "5") (pinfunction "~{RI}_5") (pintype "bidirectional"))
    )
    (net (code "77") (name "unconnected-(U10-(ADC2:2{slash}TOUCH2{slash}RTC12{slash}SPIWP)GPIO2-Pad22)") (class "Default")
      (node (ref "U10") (pin "22") (pinfunction "(ADC2:2/TOUCH2/RTC12/SPIWP)GPIO2_22") (pintype "bidirectional"))
    )
    (net (code "78") (name "unconnected-(U10-(GPIO12{slash}ADC2:5{slash}TOUCH5{slash}RTC15{slash}SPIQ)MTDI-Pad18)") (class "Default")
      (node (ref "U10") (pin "18") (pinfunction "(GPIO12/ADC2:5/TOUCH5/RTC15/SPIQ)MTDI_18") (pintype "bidirectional"))
    )
    (net (code "79") (name "unconnected-(U10-(GPIO15{slash}ADC2:3{slash}TOUCH3{slash}RTC13{slash}SPICSO{slash}U0RTS)MTDO-Pad21)") (class "Default")
      (node (ref "U10") (pin "21") (pinfunction "(GPIO15/ADC2:3/TOUCH3/RTC13/SPICSO/U0RTS)MTDO_21") (pintype "bidirectional"))
    )
    (net (code "80") (name "unconnected-(U10-(HS1_DATA4)GPIO16-Pad25)") (class "Default")
      (node (ref "U10") (pin "25") (pinfunction "(HS1_DATA4)GPIO16_25") (pintype "bidirectional"))
    )
    (net (code "81") (name "unconnected-(U10-(HS1_DATA5)GPIO17-Pad27)") (class "Default")
      (node (ref "U10") (pin "27") (pinfunction "(HS1_DATA5)GPIO17_27") (pintype "bidirectional"))
    )
    (net (code "82") (name "unconnected-(U10-(VSPIHD{slash}HS2_CMD)GPIO21-Pad42)") (class "Default")
      (node (ref "U10") (pin "42") (pinfunction "(VSPIHD/HS2_CMD)GPIO21_42") (pintype "bidirectional"))
    )
    (net (code "83") (name "unconnected-(U10-(VSPIWP{slash}HS2_CLK)GPIO22-Pad39)") (class "Default")
      (node (ref "U10") (pin "39") (pinfunction "(VSPIWP/HS2_CLK)GPIO22_39") (pintype "bidirectional"))
    )
    (net (code "84") (name "unconnected-(U10-SENSOR_CAPP(GPI37{slash}ADC1:1{slash}RTC1)-Pad6)") (class "Default")
      (node (ref "U10") (pin "6") (pinfunction "SENSOR_CAPP(GPI37/ADC1:1/RTC1)_6") (pintype "bidirectional"))
    )
    (net (code "85") (name "unconnected-(U10-VDET_1(GPI34{slash}ADC1:6)-Pad10)") (class "Default")
      (node (ref "U10") (pin "10") (pinfunction "VDET_1(GPI34/ADC1:6)_10") (pintype "bidirectional"))
    )
    (net (code "86") (name "unconnected-(U10-VDET_2(GPI35{slash}ADC1:7)-Pad11)") (class "Default")
      (node (ref "U10") (pin "11") (pinfunction "VDET_2(GPI35/ADC1:7)_11") (pintype "bidirectional"))
    )
  )
)
